# sustentationAvecPC.net
KiCad netlist of a schematic drawn in Altium Designer
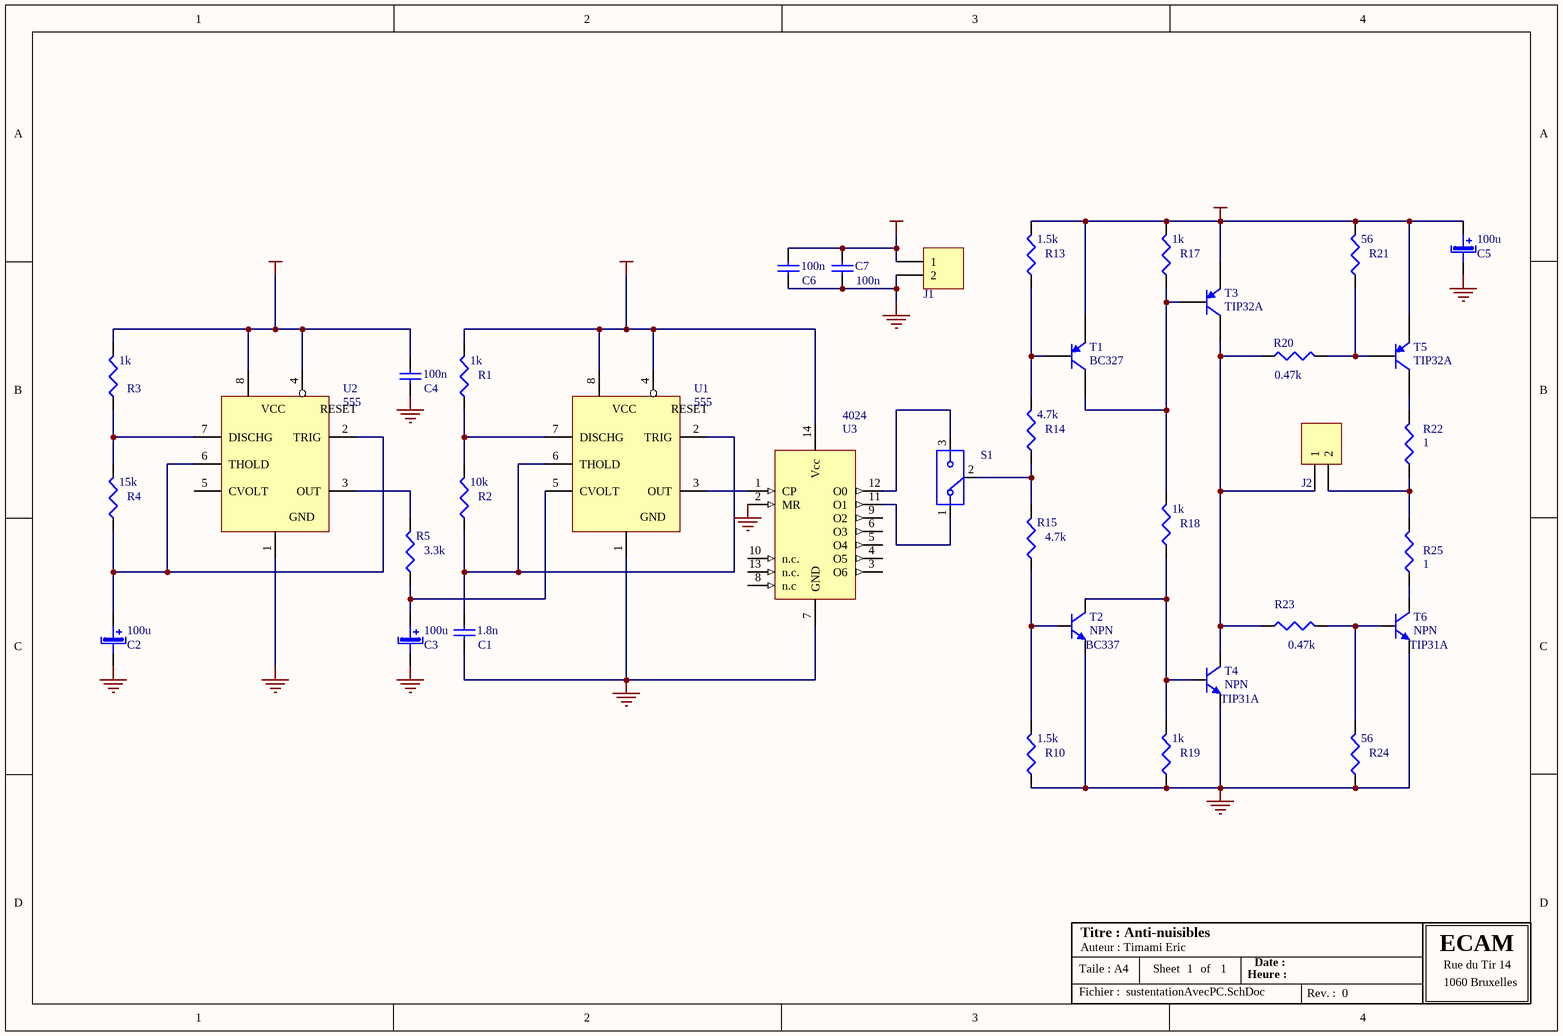
[diagram p0: sustentationAvecPC.SchDoc]

(export (version "E")
  (design (tool "Eeschema 10.0.6"))
  (components
    (comp (ref "C1")
      (value "1.8n")
      (footprint "Capa_1.8n")
      (description "Condensateur")
      (fields (field (name "DESIGNER") "ECAM 2004"))
      (libsource (lib "AntiNuisibles") (part "Condensateur"))
    )
    (comp (ref "C2")
      (value "100u")
      (footprint "CAPPR_100n")
      (description "Condensateur polatisé")
      (fields (field (name "Comment") "Cond pol radial") (field (name "DESIGNER") "ECAM 2004"))
      (libsource (lib "AntiNuisibles") (part "Cond pol radial"))
    )
    (comp (ref "C3")
      (value "100u")
      (footprint "CAPPR_100n")
      (description "Condensateur polatisé")
      (fields (field (name "Comment") "Cond pol radial") (field (name "DESIGNER") "ECAM 2004"))
      (libsource (lib "AntiNuisibles") (part "Cond pol radial"))
    )
    (comp (ref "C4")
      (value "100n")
      (footprint "cap100n")
      (description "Condensateur")
      (fields (field (name "DESIGNER") "ECAM 2004"))
      (libsource (lib "AntiNuisibles") (part "Condensateur"))
    )
    (comp (ref "C5")
      (value "100u")
      (footprint "CAPPR_100n")
      (description "Condensateur polatisé")
      (fields (field (name "Comment") "Cond pol radial") (field (name "DESIGNER") "ECAM 2004"))
      (libsource (lib "AntiNuisibles") (part "Cond pol radial"))
    )
    (comp (ref "C6")
      (value "100n")
      (footprint "cap100n")
      (description "Condensateur")
      (fields (field (name "DESIGNER") "ECAM 2004"))
      (libsource (lib "AntiNuisibles") (part "Condensateur"))
    )
    (comp (ref "C7")
      (value "100n")
      (footprint "cap100n")
      (description "Condensateur")
      (fields (field (name "DESIGNER") "ECAM 2004"))
      (libsource (lib "AntiNuisibles") (part "Condensateur"))
    )
    (comp (ref "J1")
      (value "Connecteur 2")
      (footprint "CONVIS-2")
      (description "Connecteur")
      (fields (field (name "DESIGNER") "ECAM 2005"))
      (libsource (lib "AntiNuisibles") (part "Connecteur 2"))
    )
    (comp (ref "J2")
      (value "Connecteur 2")
      (footprint "CONVIS-2")
      (description "Connecteur")
      (fields (field (name "DESIGNER") "ECAM 2005"))
      (libsource (lib "") (part "Connecteur 2_1"))
    )
    (comp (ref "R1")
      (value "1k")
      (footprint "AXIAL-0.4")
      (description "Résistance standard")
      (fields (field (name "Comment") "Résistance") (field (name "DESIGNER") "ECAM 2005"))
      (libsource (lib "AntiNuisibles") (part "Résistance"))
    )
    (comp (ref "R2")
      (value "10k")
      (footprint "AXIAL-0.4")
      (description "Résistance standard")
      (fields (field (name "Comment") "Résistance") (field (name "DESIGNER") "ECAM 2005"))
      (libsource (lib "AntiNuisibles") (part "Résistance"))
    )
    (comp (ref "R3")
      (value "1k")
      (footprint "AXIAL-0.4")
      (description "Résistance standard")
      (fields (field (name "Comment") "Résistance") (field (name "DESIGNER") "ECAM 2005"))
      (libsource (lib "AntiNuisibles") (part "Résistance"))
    )
    (comp (ref "R4")
      (value "15k")
      (footprint "AXIAL-0.4")
      (description "Résistance standard")
      (fields (field (name "Comment") "Résistance") (field (name "DESIGNER") "ECAM 2005"))
      (libsource (lib "AntiNuisibles") (part "Résistance"))
    )
    (comp (ref "R5")
      (value "3.3k")
      (footprint "AXIAL-0.4")
      (description "Résistance standard")
      (fields (field (name "Comment") "Résistance") (field (name "DESIGNER") "ECAM 2005"))
      (libsource (lib "AntiNuisibles") (part "Résistance"))
    )
    (comp (ref "R10")
      (value "1.5k")
      (footprint "AXIAL-0.4")
      (description "Résistance standard")
      (fields (field (name "Comment") "Résistance") (field (name "DESIGNER") "ECAM 2005"))
      (libsource (lib "AntiNuisibles") (part "Résistance"))
    )
    (comp (ref "R13")
      (value "1.5k")
      (footprint "AXIAL-0.4")
      (description "Résistance standard")
      (fields (field (name "Comment") "Résistance") (field (name "DESIGNER") "ECAM 2005"))
      (libsource (lib "AntiNuisibles") (part "Résistance"))
    )
    (comp (ref "R14")
      (value "4.7k")
      (footprint "AXIAL-0.4")
      (description "Résistance standard")
      (fields (field (name "Comment") "Résistance") (field (name "DESIGNER") "ECAM 2005"))
      (libsource (lib "AntiNuisibles") (part "Résistance"))
    )
    (comp (ref "R15")
      (value "4.7k")
      (footprint "AXIAL-0.4")
      (description "Résistance standard")
      (fields (field (name "Comment") "Résistance") (field (name "DESIGNER") "ECAM 2005"))
      (libsource (lib "AntiNuisibles") (part "Résistance"))
    )
    (comp (ref "R17")
      (value "1k")
      (footprint "AXIAL-0.4")
      (description "Résistance standard")
      (fields (field (name "Comment") "Résistance") (field (name "DESIGNER") "ECAM 2005"))
      (libsource (lib "AntiNuisibles") (part "Résistance"))
    )
    (comp (ref "R18")
      (value "1k")
      (footprint "AXIAL-0.4")
      (description "Résistance standard")
      (fields (field (name "Comment") "Résistance") (field (name "DESIGNER") "ECAM 2005"))
      (libsource (lib "AntiNuisibles") (part "Résistance"))
    )
    (comp (ref "R19")
      (value "1k")
      (footprint "AXIAL-0.4")
      (description "Résistance standard")
      (fields (field (name "Comment") "Résistance") (field (name "DESIGNER") "ECAM 2005"))
      (libsource (lib "AntiNuisibles") (part "Résistance"))
    )
    (comp (ref "R20")
      (value "0.47k")
      (footprint "AXIAL-0.4_vertical-")
      (description "Résistance standard")
      (fields (field (name "Comment") "Résistance") (field (name "DESIGNER") "ECAM 2005"))
      (libsource (lib "AntiNuisibles") (part "Résistance"))
    )
    (comp (ref "R21")
      (value "56")
      (footprint "AXIAL-0.4")
      (description "Résistance standard")
      (fields (field (name "Comment") "Résistance") (field (name "DESIGNER") "ECAM 2005"))
      (libsource (lib "AntiNuisibles") (part "Résistance"))
    )
    (comp (ref "R22")
      (value "1")
      (footprint "AXIAL-0.5_de_puissance")
      (description "Résistance standard")
      (fields (field (name "Comment") "Résistance") (field (name "DESIGNER") "ECAM 2005"))
      (libsource (lib "AntiNuisibles") (part "Résistance"))
    )
    (comp (ref "R23")
      (value "0.47k")
      (footprint "AXIAL-0.4_vertical-")
      (description "Résistance standard")
      (fields (field (name "Comment") "Résistance") (field (name "DESIGNER") "ECAM 2005"))
      (libsource (lib "AntiNuisibles") (part "Résistance"))
    )
    (comp (ref "R24")
      (value "56")
      (footprint "AXIAL-0.4")
      (description "Résistance standard")
      (fields (field (name "Comment") "Résistance") (field (name "DESIGNER") "ECAM 2005"))
      (libsource (lib "AntiNuisibles") (part "Résistance"))
    )
    (comp (ref "R25")
      (value "1")
      (footprint "AXIAL-0.5_de_puissance")
      (description "Résistance standard")
      (fields (field (name "Comment") "Résistance") (field (name "DESIGNER") "ECAM 2005"))
      (libsource (lib "AntiNuisibles") (part "Résistance"))
    )
    (comp (ref "S1")
      (value "DIP Inverseur")
      (footprint "SIP3")
      (description "Inverseur")
      (fields (field (name "DESIGNER") "ECAM 2003"))
      (libsource (lib "AntiNuisibles") (part "DIP Inverseur"))
    )
    (comp (ref "T1")
      (value "BC327")
      (footprint "TO-226AE_BC327")
      (description "PNP BISS-Transistor")
      (fields (field (name "PUBLISHER") "Altium Limited"))
      (libsource (lib "AntiNuisibles") (part "BDL32_1"))
    )
    (comp (ref "T2")
      (value "BC337")
      (footprint "TO-226AE_BC327")
      (description "Transistor Bipolaire")
      (fields (field (name "ALTIUM_VALUE") "NPN") (field (name "DESIGNER") "ECAM 2002"))
      (libsource (lib "AntiNuisibles") (part "NPN_1"))
    )
    (comp (ref "T3")
      (value "TIP32A")
      (footprint "TO-220")
      (description "PNP BISS-Transistor")
      (fields (field (name "PUBLISHER") "Altium Limited"))
      (libsource (lib "AntiNuisibles") (part "BDL32"))
    )
    (comp (ref "T4")
      (value "TIP31A")
      (footprint "TO-220")
      (description "Transistor Bipolaire")
      (fields (field (name "ALTIUM_VALUE") "NPN") (field (name "DESIGNER") "ECAM 2002"))
      (libsource (lib "AntiNuisibles") (part "NPN_2"))
    )
    (comp (ref "T5")
      (value "TIP32A")
      (footprint "TO-220")
      (description "PNP BISS-Transistor")
      (fields (field (name "PUBLISHER") "Altium Limited"))
      (libsource (lib "AntiNuisibles") (part "BDL32"))
    )
    (comp (ref "T6")
      (value "TIP31A")
      (footprint "TO-220")
      (description "Transistor Bipolaire")
      (fields (field (name "ALTIUM_VALUE") "NPN") (field (name "DESIGNER") "ECAM 2002"))
      (libsource (lib "AntiNuisibles") (part "NPN_2"))
    )
    (comp (ref "U1")
      (value "555")
      (footprint "DIP8")
      (description "Timer")
      (libsource (lib "AntiNuisibles") (part "555"))
    )
    (comp (ref "U2")
      (value "555")
      (footprint "DIP8")
      (description "Timer")
      (libsource (lib "AntiNuisibles") (part "555"))
    )
    (comp (ref "U3")
      (value "4024")
      (footprint "DIP14")
      (description "compteur")
      (fields (field (name "PUBLISHER") "Altium Limited"))
      (libsource (lib "AntiNuisibles") (part "4024"))
    )
  )
  (nets
    (net (code "1") (name "GND") (class "Default")
      (node (ref "C1") (pin "2") (pinfunction "2_2") (pintype "passive"))
      (node (ref "C2") (pin "2") (pinfunction "-_2") (pintype "passive"))
      (node (ref "C3") (pin "2") (pinfunction "-_2") (pintype "passive"))
      (node (ref "C4") (pin "2") (pinfunction "2_2") (pintype "passive"))
      (node (ref "C5") (pin "2") (pinfunction "-_2") (pintype "passive"))
      (node (ref "C6") (pin "2") (pinfunction "2_2") (pintype "passive"))
      (node (ref "C7") (pin "2") (pinfunction "2_2") (pintype "passive"))
      (node (ref "J1") (pin "2") (pinfunction "2_2") (pintype "passive"))
      (node (ref "R10") (pin "1") (pinfunction "1_1") (pintype "passive"))
      (node (ref "R19") (pin "1") (pinfunction "1_1") (pintype "passive"))
      (node (ref "R24") (pin "1") (pinfunction "1_1") (pintype "passive"))
      (node (ref "T2") (pin "3") (pinfunction "E_3") (pintype "passive"))
      (node (ref "T4") (pin "3") (pinfunction "E_3") (pintype "passive"))
      (node (ref "T6") (pin "3") (pinfunction "E_3") (pintype "passive"))
      (node (ref "U1") (pin "1") (pinfunction "GND_1") (pintype "passive"))
      (node (ref "U2") (pin "1") (pinfunction "GND_1") (pintype "passive"))
      (node (ref "U3") (pin "2") (pinfunction "MR_2") (pintype "input"))
      (node (ref "U3") (pin "7") (pinfunction "GND_7") (pintype "power_in"))
    )
    (net (code "2") (name "Net-(C2-+)") (class "Default")
      (node (ref "C2") (pin "1") (pinfunction "+_1") (pintype "passive"))
      (node (ref "R4") (pin "1") (pinfunction "1_1") (pintype "passive"))
      (node (ref "U2") (pin "2") (pinfunction "TRIG_2") (pintype "passive"))
      (node (ref "U2") (pin "6") (pinfunction "THOLD_6") (pintype "passive"))
    )
    (net (code "3") (name "Net-(C3-+)") (class "Default")
      (node (ref "C3") (pin "1") (pinfunction "+_1") (pintype "passive"))
      (node (ref "R5") (pin "1") (pinfunction "1_1") (pintype "passive"))
      (node (ref "U1") (pin "5") (pinfunction "CVOLT_5") (pintype "passive"))
    )
    (net (code "4") (name "Net-(J2-Pad2)") (class "Default")
      (node (ref "J2") (pin "2") (pinfunction "2_2") (pintype "passive"))
      (node (ref "R22") (pin "1") (pinfunction "1_1") (pintype "passive"))
      (node (ref "R25") (pin "2") (pinfunction "2_2") (pintype "passive"))
    )
    (net (code "5") (name "Net-(S1-COM)") (class "Default")
      (node (ref "R14") (pin "1") (pinfunction "1_1") (pintype "passive"))
      (node (ref "R15") (pin "2") (pinfunction "2_2") (pintype "passive"))
      (node (ref "S1") (pin "2") (pinfunction "COM_2") (pintype "passive"))
    )
    (net (code "6") (name "Net-(S1-TA)") (class "Default")
      (node (ref "S1") (pin "1") (pinfunction "TA_1") (pintype "passive"))
      (node (ref "U3") (pin "11") (pinfunction "O1_11") (pintype "output"))
    )
    (net (code "7") (name "Net-(S1-TB)") (class "Default")
      (node (ref "S1") (pin "3") (pinfunction "TB_3") (pintype "passive"))
      (node (ref "U3") (pin "12") (pinfunction "O0_12") (pintype "output"))
    )
    (net (code "8") (name "Net-(T1-B)") (class "Default")
      (node (ref "R13") (pin "1") (pinfunction "1_1") (pintype "passive"))
      (node (ref "R14") (pin "2") (pinfunction "2_2") (pintype "passive"))
      (node (ref "T1") (pin "2") (pinfunction "B_2") (pintype "passive"))
    )
    (net (code "9") (name "Net-(T1-C)") (class "Default")
      (node (ref "R17") (pin "1") (pinfunction "1_1") (pintype "passive"))
      (node (ref "R18") (pin "2") (pinfunction "2_2") (pintype "passive"))
      (node (ref "T1") (pin "3") (pinfunction "C_3") (pintype "passive"))
      (node (ref "T3") (pin "1") (pinfunction "B_1") (pintype "passive"))
    )
    (net (code "10") (name "Net-(T2-B)") (class "Default")
      (node (ref "R10") (pin "2") (pinfunction "2_2") (pintype "passive"))
      (node (ref "R15") (pin "1") (pinfunction "1_1") (pintype "passive"))
      (node (ref "T2") (pin "2") (pinfunction "B_2") (pintype "passive"))
    )
    (net (code "11") (name "Net-(T2-C)") (class "Default")
      (node (ref "R18") (pin "1") (pinfunction "1_1") (pintype "passive"))
      (node (ref "R19") (pin "2") (pinfunction "2_2") (pintype "passive"))
      (node (ref "T2") (pin "1") (pinfunction "C_1") (pintype "passive"))
      (node (ref "T4") (pin "1") (pinfunction "B_1") (pintype "passive"))
    )
    (net (code "12") (name "Net-(T3-C)") (class "Default")
      (node (ref "J2") (pin "1") (pinfunction "1_1") (pintype "passive"))
      (node (ref "R20") (pin "1") (pinfunction "1_1") (pintype "passive"))
      (node (ref "R23") (pin "1") (pinfunction "1_1") (pintype "passive"))
      (node (ref "T3") (pin "2") (pinfunction "C_2") (pintype "passive"))
      (node (ref "T4") (pin "2") (pinfunction "C_2") (pintype "passive"))
    )
    (net (code "13") (name "Net-(T5-B)") (class "Default")
      (node (ref "R20") (pin "2") (pinfunction "2_2") (pintype "passive"))
      (node (ref "R21") (pin "1") (pinfunction "1_1") (pintype "passive"))
      (node (ref "T5") (pin "1") (pinfunction "B_1") (pintype "passive"))
    )
    (net (code "14") (name "Net-(T5-C)") (class "Default")
      (node (ref "R22") (pin "2") (pinfunction "2_2") (pintype "passive"))
      (node (ref "T5") (pin "2") (pinfunction "C_2") (pintype "passive"))
    )
    (net (code "15") (name "Net-(T6-B)") (class "Default")
      (node (ref "R23") (pin "2") (pinfunction "2_2") (pintype "passive"))
      (node (ref "R24") (pin "2") (pinfunction "2_2") (pintype "passive"))
      (node (ref "T6") (pin "1") (pinfunction "B_1") (pintype "passive"))
    )
    (net (code "16") (name "Net-(T6-C)") (class "Default")
      (node (ref "R25") (pin "1") (pinfunction "1_1") (pintype "passive"))
      (node (ref "T6") (pin "2") (pinfunction "C_2") (pintype "passive"))
    )
    (net (code "17") (name "Net-(U1-DISCHG)") (class "Default")
      (node (ref "R1") (pin "1") (pinfunction "1_1") (pintype "passive"))
      (node (ref "R2") (pin "2") (pinfunction "2_2") (pintype "passive"))
      (node (ref "U1") (pin "7") (pinfunction "DISCHG_7") (pintype "passive"))
    )
    (net (code "18") (name "Net-(U1-OUT)") (class "Default")
      (node (ref "U1") (pin "3") (pinfunction "OUT_3") (pintype "passive"))
      (node (ref "U3") (pin "1") (pinfunction "CP_1") (pintype "input"))
    )
    (net (code "19") (name "Net-(U1-THOLD)") (class "Default")
      (node (ref "C1") (pin "1") (pinfunction "1_1") (pintype "passive"))
      (node (ref "R2") (pin "1") (pinfunction "1_1") (pintype "passive"))
      (node (ref "U1") (pin "2") (pinfunction "TRIG_2") (pintype "passive"))
      (node (ref "U1") (pin "6") (pinfunction "THOLD_6") (pintype "passive"))
    )
    (net (code "20") (name "Net-(U2-DISCHG)") (class "Default")
      (node (ref "R3") (pin "1") (pinfunction "1_1") (pintype "passive"))
      (node (ref "R4") (pin "2") (pinfunction "2_2") (pintype "passive"))
      (node (ref "U2") (pin "7") (pinfunction "DISCHG_7") (pintype "passive"))
    )
    (net (code "21") (name "Net-(U2-OUT)") (class "Default")
      (node (ref "R5") (pin "2") (pinfunction "2_2") (pintype "passive"))
      (node (ref "U2") (pin "3") (pinfunction "OUT_3") (pintype "passive"))
    )
    (net (code "22") (name "VCC") (class "Default")
      (node (ref "C4") (pin "1") (pinfunction "1_1") (pintype "passive"))
      (node (ref "C5") (pin "1") (pinfunction "+_1") (pintype "passive"))
      (node (ref "C6") (pin "1") (pinfunction "1_1") (pintype "passive"))
      (node (ref "C7") (pin "1") (pinfunction "1_1") (pintype "passive"))
      (node (ref "J1") (pin "1") (pinfunction "1_1") (pintype "passive"))
      (node (ref "R1") (pin "2") (pinfunction "2_2") (pintype "passive"))
      (node (ref "R13") (pin "2") (pinfunction "2_2") (pintype "passive"))
      (node (ref "R17") (pin "2") (pinfunction "2_2") (pintype "passive"))
      (node (ref "R21") (pin "2") (pinfunction "2_2") (pintype "passive"))
      (node (ref "R3") (pin "2") (pinfunction "2_2") (pintype "passive"))
      (node (ref "T1") (pin "1") (pinfunction "E_1") (pintype "passive"))
      (node (ref "T3") (pin "3") (pinfunction "E_3") (pintype "passive"))
      (node (ref "T5") (pin "3") (pinfunction "E_3") (pintype "passive"))
      (node (ref "U1") (pin "4") (pinfunction "RESET_4") (pintype "passive"))
      (node (ref "U1") (pin "8") (pinfunction "VCC_8") (pintype "passive"))
      (node (ref "U2") (pin "4") (pinfunction "RESET_4") (pintype "passive"))
      (node (ref "U2") (pin "8") (pinfunction "VCC_8") (pintype "passive"))
      (node (ref "U3") (pin "14") (pinfunction "Vcc_14") (pintype "power_in"))
    )
    (net (code "23") (name "unconnected-(U2-CVOLT-Pad5)") (class "Default")
      (node (ref "U2") (pin "5") (pinfunction "CVOLT_5") (pintype "passive"))
    )
    (net (code "24") (name "unconnected-(U3-O2-Pad9)") (class "Default")
      (node (ref "U3") (pin "9") (pinfunction "O2_9") (pintype "output"))
    )
    (net (code "25") (name "unconnected-(U3-O3-Pad6)") (class "Default")
      (node (ref "U3") (pin "6") (pinfunction "O3_6") (pintype "output"))
    )
    (net (code "26") (name "unconnected-(U3-O4-Pad5)") (class "Default")
      (node (ref "U3") (pin "5") (pinfunction "O4_5") (pintype "output"))
    )
    (net (code "27") (name "unconnected-(U3-O5-Pad4)") (class "Default")
      (node (ref "U3") (pin "4") (pinfunction "O5_4") (pintype "output"))
    )
    (net (code "28") (name "unconnected-(U3-O6-Pad3)") (class "Default")
      (node (ref "U3") (pin "3") (pinfunction "O6_3") (pintype "output"))
    )
    (net (code "29") (name "unconnected-(U3-n.c-Pad8)") (class "Default")
      (node (ref "U3") (pin "8") (pinfunction "n.c_8") (pintype "input"))
    )
    (net (code "30") (name "unconnected-(U3-n.c.-Pad10)") (class "Default")
      (node (ref "U3") (pin "10") (pinfunction "n.c._10") (pintype "input"))
    )
    (net (code "31") (name "unconnected-(U3-n.c.-Pad13)") (class "Default")
      (node (ref "U3") (pin "13") (pinfunction "n.c._13") (pintype "input"))
    )
  )
)
